# LIXIE_II_Main_V4.net
KiCad netlist of a schematic drawn in EAGLE
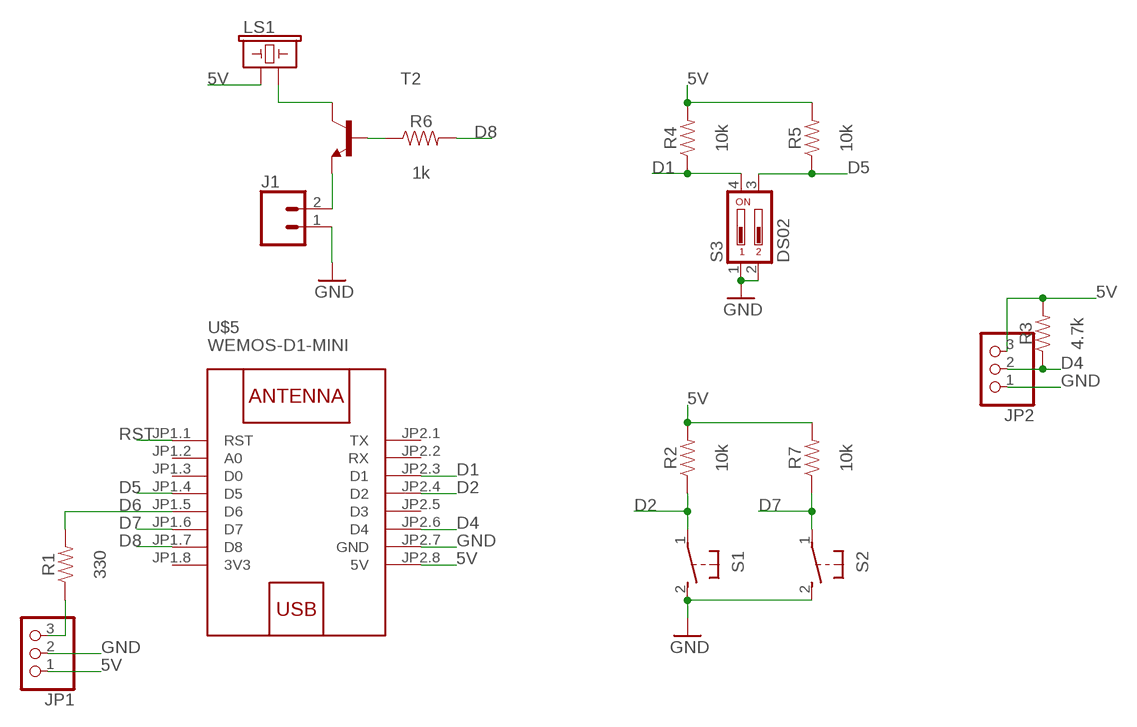
[diagram p0: schematic, sheet 1]

(export (version "E")
  (design (tool "Eeschema 10.0.6"))
  (components
    (comp (ref "J1")
      (value "CONN_02")
      (footprint "eagle-import:1X02")
      (libsource (lib "eagle-import") (part "CONN_02"))
    )
    (comp (ref "JP1")
      (value "PINHD-1X3")
      (footprint "eagle-import:1X03")
      (libsource (lib "eagle-import") (part "PINHD-1X3"))
    )
    (comp (ref "JP2")
      (value "PINHD-1X3")
      (footprint "eagle-import:1X03")
      (libsource (lib "eagle-import") (part "PINHD-1X3"))
    )
    (comp (ref "LS1")
      (value "BUZZER-PTH")
      (footprint "eagle-import:BUZZER-12MM")
      (libsource (lib "eagle-import") (part "BUZZER-PTH"))
    )
    (comp (ref "R1")
      (value "330")
      (footprint "eagle-import:0805")
      (libsource (lib "eagle-import") (part "0.3OHM-0805-1/8W-1%"))
    )
    (comp (ref "R2")
      (value "10k")
      (footprint "eagle-import:0805")
      (libsource (lib "eagle-import") (part "0.3OHM-0805-1/8W-1%"))
    )
    (comp (ref "R3")
      (value "4.7k")
      (footprint "eagle-import:0805")
      (libsource (lib "eagle-import") (part "0.3OHM-0805-1/8W-1%"))
    )
    (comp (ref "R4")
      (value "10k")
      (footprint "eagle-import:0805")
      (libsource (lib "eagle-import") (part "0.3OHM-0805-1/8W-1%"))
    )
    (comp (ref "R5")
      (value "10k")
      (footprint "eagle-import:0805")
      (libsource (lib "eagle-import") (part "0.3OHM-0805-1/8W-1%"))
    )
    (comp (ref "R6")
      (value "1k")
      (footprint "eagle-import:0805")
      (libsource (lib "eagle-import") (part "0.3OHM-0805-1/8W-1%"))
    )
    (comp (ref "R7")
      (value "10k")
      (footprint "eagle-import:0805")
      (libsource (lib "eagle-import") (part "0.3OHM-0805-1/8W-1%"))
    )
    (comp (ref "S1")
      (value "31-XX")
      (footprint "eagle-import:B3F-31XX")
      (libsource (lib "eagle-import") (part "31-XX"))
    )
    (comp (ref "S2")
      (value "31-XX")
      (footprint "eagle-import:B3F-31XX")
      (libsource (lib "eagle-import") (part "31-XX"))
    )
    (comp (ref "S3")
      (value "DS02")
      (footprint "eagle-import:DS-02")
      (fields (field (name "MPN") "MCNDS02"))
      (libsource (lib "eagle-import") (part "DS02"))
    )
    (comp (ref "T2")
      (value "-NPN-SOT23-EBC")
      (footprint "eagle-import:SOT23-EBC")
      (libsource (lib "eagle-import") (part "-NPN-SOT23-EBC"))
    )
    (comp (ref "U$5")
      (value "WEMOS-D1-MINI")
      (footprint "eagle-import:WEMOS-D1-MINI")
      (libsource (lib "eagle-import") (part "WEMOS-D1-MINI"))
    )
  )
  (nets
    (net (code "1") (name "/3V3") (class "Default")
      (node (ref "U$5") (pin "JP1.8") (pinfunction "3V3_JP1.8") (pintype "power_in"))
    )
    (net (code "2") (name "/5V") (class "Default")
      (node (ref "JP1") (pin "1") (pinfunction "1_1") (pintype "passive"))
      (node (ref "JP2") (pin "3") (pinfunction "3_3") (pintype "passive"))
      (node (ref "LS1") (pin "+") (pinfunction "1_+") (pintype "passive"))
      (node (ref "R2") (pin "2") (pinfunction "2_2") (pintype "passive"))
      (node (ref "R3") (pin "2") (pinfunction "2_2") (pintype "passive"))
      (node (ref "R4") (pin "2") (pinfunction "2_2") (pintype "passive"))
      (node (ref "R5") (pin "2") (pinfunction "2_2") (pintype "passive"))
      (node (ref "R7") (pin "2") (pinfunction "2_2") (pintype "passive"))
      (node (ref "U$5") (pin "JP2.8") (pinfunction "5V_JP2.8") (pintype "power_in"))
    )
    (net (code "3") (name "/D1") (class "Default")
      (node (ref "R4") (pin "1") (pinfunction "1_1") (pintype "passive"))
      (node (ref "S3") (pin "4") (pinfunction "4_4") (pintype "passive"))
      (node (ref "U$5") (pin "JP2.3") (pinfunction "D1_JP2.3") (pintype "bidirectional"))
    )
    (net (code "4") (name "/D2") (class "Default")
      (node (ref "R2") (pin "1") (pinfunction "1_1") (pintype "passive"))
      (node (ref "S1") (pin "1") (pinfunction "P_1") (pintype "passive"))
      (node (ref "U$5") (pin "JP2.4") (pinfunction "D2_JP2.4") (pintype "bidirectional"))
    )
    (net (code "5") (name "/D4") (class "Default")
      (node (ref "JP2") (pin "2") (pinfunction "2_2") (pintype "passive"))
      (node (ref "R3") (pin "1") (pinfunction "1_1") (pintype "passive"))
      (node (ref "U$5") (pin "JP2.6") (pinfunction "D4_JP2.6") (pintype "bidirectional"))
    )
    (net (code "6") (name "/D5") (class "Default")
      (node (ref "R5") (pin "1") (pinfunction "1_1") (pintype "passive"))
      (node (ref "S3") (pin "3") (pinfunction "3_3") (pintype "passive"))
      (node (ref "U$5") (pin "JP1.4") (pinfunction "D5_JP1.4") (pintype "bidirectional"))
    )
    (net (code "7") (name "/D6") (class "Default")
      (node (ref "R1") (pin "2") (pinfunction "2_2") (pintype "passive"))
      (node (ref "U$5") (pin "JP1.5") (pinfunction "D6_JP1.5") (pintype "bidirectional"))
    )
    (net (code "8") (name "/D7") (class "Default")
      (node (ref "R7") (pin "1") (pinfunction "1_1") (pintype "passive"))
      (node (ref "S2") (pin "1") (pinfunction "P_1") (pintype "passive"))
      (node (ref "U$5") (pin "JP1.6") (pinfunction "D7_JP1.6") (pintype "bidirectional"))
    )
    (net (code "9") (name "/D8") (class "Default")
      (node (ref "R6") (pin "2") (pinfunction "2_2") (pintype "passive"))
      (node (ref "U$5") (pin "JP1.7") (pinfunction "D8_JP1.7") (pintype "bidirectional"))
    )
    (net (code "10") (name "/RST") (class "Default")
      (node (ref "U$5") (pin "JP1.1") (pinfunction "RST_JP1.1") (pintype "bidirectional"))
    )
    (net (code "11") (name "GND") (class "Default")
      (node (ref "J1") (pin "1") (pinfunction "1_1") (pintype "passive"))
      (node (ref "JP1") (pin "2") (pinfunction "2_2") (pintype "passive"))
      (node (ref "JP2") (pin "1") (pinfunction "1_1") (pintype "passive"))
      (node (ref "S1") (pin "2") (pinfunction "S_2") (pintype "passive"))
      (node (ref "S2") (pin "2") (pinfunction "S_2") (pintype "passive"))
      (node (ref "S3") (pin "1") (pinfunction "1_1") (pintype "passive"))
      (node (ref "S3") (pin "2") (pinfunction "2_2") (pintype "passive"))
      (node (ref "U$5") (pin "JP2.7") (pinfunction "GND_JP2.7") (pintype "power_in"))
    )
    (net (code "12") (name "Net-(J1-Pad2)") (class "Default")
      (node (ref "J1") (pin "2") (pinfunction "2_2") (pintype "passive"))
      (node (ref "T2") (pin "E") (pinfunction "E_E") (pintype "passive"))
    )
    (net (code "13") (name "Net-(JP1-Pad3)") (class "Default")
      (node (ref "JP1") (pin "3") (pinfunction "3_3") (pintype "passive"))
      (node (ref "R1") (pin "1") (pinfunction "1_1") (pintype "passive"))
    )
    (net (code "14") (name "Net-(LS1-2)") (class "Default")
      (node (ref "LS1") (pin "-") (pinfunction "2_-") (pintype "passive"))
      (node (ref "T2") (pin "C") (pinfunction "C_C") (pintype "passive"))
    )
    (net (code "15") (name "Net-(R6-Pad1)") (class "Default")
      (node (ref "R6") (pin "1") (pinfunction "1_1") (pintype "passive"))
      (node (ref "T2") (pin "B") (pinfunction "B_B") (pintype "passive"))
    )
    (net (code "16") (name "unconnected-(U$5-A0-PadJP1.2)") (class "Default")
      (node (ref "U$5") (pin "JP1.2") (pinfunction "A0_JP1.2") (pintype "bidirectional"))
    )
    (net (code "17") (name "unconnected-(U$5-D0-PadJP1.3)") (class "Default")
      (node (ref "U$5") (pin "JP1.3") (pinfunction "D0_JP1.3") (pintype "bidirectional"))
    )
    (net (code "18") (name "unconnected-(U$5-D3-PadJP2.5)") (class "Default")
      (node (ref "U$5") (pin "JP2.5") (pinfunction "D3_JP2.5") (pintype "bidirectional"))
    )
    (net (code "19") (name "unconnected-(U$5-RX-PadJP2.2)") (class "Default")
      (node (ref "U$5") (pin "JP2.2") (pinfunction "RX_JP2.2") (pintype "bidirectional"))
    )
    (net (code "20") (name "unconnected-(U$5-TX-PadJP2.1)") (class "Default")
      (node (ref "U$5") (pin "JP2.1") (pinfunction "TX_JP2.1") (pintype "bidirectional"))
    )
  )
)
